# 4_WiFi.net
KiCad netlist of a schematic drawn in Altium Designer
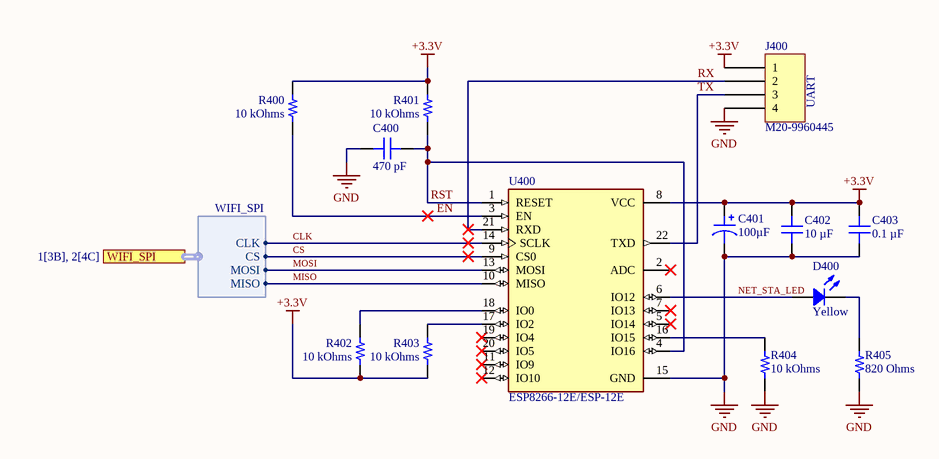
[diagram p0: 4_WiFi.SchDoc]

(export (version "E")
  (design (tool "Eeschema 10.0.6"))
  (components
    (comp (ref "C400")
      (value "470 pF")
      (footprint "CAP 0603_1608")
      (description "CAP CER 470PF 50V X7R 0603")
      (fields
        (field (name "PART NUMBER") "CL10B471KB8NNNC")
        (field (name "CAPACITANCE") "470 pF")
        (field (name "MANUFACTURER") "Samsung Electro-Mechanics")
      )
      (libsource (lib "Celestial Altium Library - altium_library") (part "Capacitor"))
    )
    (comp (ref "C401")
      (value "100µF")
      (footprint "CAP POL 2917_7343")
      (description "CAP TANT 100UF 10% 16V 2917")
      (fields (field (name "PART NUMBER") "TAJD107K016RNJ") (field (name "MANUFACTURER") "AVX Corporation"))
      (libsource (lib "Celestial Altium Library - altium_library") (part "Polarised Capacitor"))
    )
    (comp (ref "C402")
      (value "10 µF")
      (footprint "CAP 0805_2012")
      (description "CAP CER 10UF 10V X7R 0805")
      (fields
        (field (name "PART NUMBER") "CL21B106KPQNNNE")
        (field (name "CAPACITANCE") "10 µF")
        (field (name "MANUFACTURER") "Samsung Electro-Mechanics")
      )
      (libsource (lib "Celestial Altium Library - altium_library") (part "Capacitor"))
    )
    (comp (ref "C403")
      (value "0.1 µF")
      (footprint "CAP 0603_1608")
      (description "CAP CER 0.1UF 25V X7R 0603")
      (fields
        (field (name "PART NUMBER") "CL10B104KA8NNNC")
        (field (name "CAPACITANCE") "0.1 µF")
        (field (name "MANUFACTURER") "Samsung Electro-Mechanics")
      )
      (libsource (lib "Celestial Altium Library - altium_library") (part "Capacitor"))
    )
    (comp (ref "D400")
      (value "Yellow")
      (footprint "LED 0603_1608 YELLOW")
      (description "LED YELLOW DIFFUSED 0603 SMD")
      (fields
        (field (name "PART NUMBER") "LY L29K-H1K2-26-Z")
        (field (name "MANUFACTURER") "OSRAM Opto Semiconductors Inc.")
      )
      (libsource (lib "Celestial Altium Library - altium_library") (part "LED"))
    )
    (comp (ref "J400")
      (value "M20-9960445")
      (footprint "HARWIN M20-9960445")
      (description "CONN HEADER R/A 4POS 2.54MM")
      (fields (field (name "MANUFACTURER") "Harwin Inc."))
      (libsource (lib "Celestial Altium Library - altium_library") (part "4 Pin"))
    )
    (comp (ref "R400")
      (value "10 kOhms")
      (footprint "RES 0603_1608")
      (description "RES SMD 10 KOHM 1% 1/5W 0603")
      (fields
        (field (name "PART NUMBER") "ERJ-P03F1002V")
        (field (name "MANUFACTURER") "Panasonic Electronic Components")
      )
      (libsource (lib "Celestial Altium Library - altium_library") (part "Resistor"))
    )
    (comp (ref "R401")
      (value "10 kOhms")
      (footprint "RES 0603_1608")
      (description "RES SMD 10 KOHM 1% 1/5W 0603")
      (fields
        (field (name "PART NUMBER") "ERJ-P03F1002V")
        (field (name "MANUFACTURER") "Panasonic Electronic Components")
      )
      (libsource (lib "Celestial Altium Library - altium_library") (part "Resistor"))
    )
    (comp (ref "R402")
      (value "10 kOhms")
      (footprint "RES 0603_1608")
      (description "RES SMD 10 KOHM 1% 1/5W 0603")
      (fields
        (field (name "PART NUMBER") "ERJ-P03F1002V")
        (field (name "MANUFACTURER") "Panasonic Electronic Components")
      )
      (libsource (lib "Celestial Altium Library - altium_library") (part "Resistor"))
    )
    (comp (ref "R403")
      (value "10 kOhms")
      (footprint "RES 0603_1608")
      (description "RES SMD 10 KOHM 1% 1/5W 0603")
      (fields
        (field (name "PART NUMBER") "ERJ-P03F1002V")
        (field (name "MANUFACTURER") "Panasonic Electronic Components")
      )
      (libsource (lib "Celestial Altium Library - altium_library") (part "Resistor"))
    )
    (comp (ref "R404")
      (value "10 kOhms")
      (footprint "RES 0603_1608")
      (description "RES SMD 10 KOHM 1% 1/5W 0603")
      (fields
        (field (name "PART NUMBER") "ERJ-P03F1002V")
        (field (name "MANUFACTURER") "Panasonic Electronic Components")
      )
      (libsource (lib "Celestial Altium Library - altium_library") (part "Resistor"))
    )
    (comp (ref "R405")
      (value "820 Ohms")
      (footprint "RES 0603_1608")
      (description "RES SMD 820 OHM 1% 1/10W 0603")
      (fields
        (field (name "PART NUMBER") "ERJ-3EKF8200V")
        (field (name "MANUFACTURER") "Panasonic Electronic Components")
      )
      (libsource (lib "Celestial Altium Library - altium_library") (part "Resistor"))
    )
    (comp (ref "U400")
      (value "ESP8266-12E/ESP-12E")
      (footprint "XCVR_ESP8266-12E/ESP-12E")
      (fields (field (name "MF") "AI-Thinker"))
      (libsource (lib "ESP8266-12E_ESP-12E") (part "ESP8266-12E/ESP-12E"))
    )
  )
  (nets
    (net (code "2") (name "+3.3V") (class "Default")
      (node (ref "C401") (pin "1") (pinfunction "1_1") (pintype "passive"))
      (node (ref "C402") (pin "1") (pinfunction "1_1") (pintype "passive"))
      (node (ref "C403") (pin "2") (pinfunction "2_2") (pintype "passive"))
      (node (ref "J400") (pin "1") (pinfunction "1_1") (pintype "passive"))
      (node (ref "R400") (pin "2") (pinfunction "2_2") (pintype "passive"))
      (node (ref "R401") (pin "2") (pinfunction "2_2") (pintype "passive"))
      (node (ref "R402") (pin "1") (pinfunction "1_1") (pintype "passive"))
      (node (ref "R403") (pin "1") (pinfunction "1_1") (pintype "passive"))
      (node (ref "U400") (pin "8") (pinfunction "VCC_8") (pintype "power_in"))
    )
    (net (code "3") (name "/CLK") (class "Default")
      (node (ref "U400") (pin "14") (pinfunction "SCLK_14") (pintype "input"))
    )
    (net (code "4") (name "/CS") (class "Default")
      (node (ref "U400") (pin "9") (pinfunction "CS0_9") (pintype "input"))
    )
    (net (code "5") (name "/EN") (class "Default")
      (node (ref "R400") (pin "1") (pinfunction "1_1") (pintype "passive"))
      (node (ref "U400") (pin "3") (pinfunction "EN_3") (pintype "input"))
    )
    (net (code "6") (name "/MISO") (class "Default")
      (node (ref "U400") (pin "10") (pinfunction "MISO_10") (pintype "bidirectional"))
    )
    (net (code "7") (name "/MOSI") (class "Default")
      (node (ref "U400") (pin "13") (pinfunction "MOSI_13") (pintype "bidirectional"))
    )
    (net (code "8") (name "/NET_STA_LED") (class "Default")
      (node (ref "D400") (pin "1") (pinfunction "1_1") (pintype "passive"))
      (node (ref "U400") (pin "6") (pinfunction "IO12_6") (pintype "bidirectional"))
    )
    (net (code "9") (name "/RST") (class "Default")
      (node (ref "C400") (pin "2") (pinfunction "2_2") (pintype "passive"))
      (node (ref "R401") (pin "1") (pinfunction "1_1") (pintype "passive"))
      (node (ref "U400") (pin "1") (pinfunction "RESET_1") (pintype "input"))
      (node (ref "U400") (pin "4") (pinfunction "IO16_4") (pintype "bidirectional"))
    )
    (net (code "10") (name "/RX") (class "Default")
      (node (ref "J400") (pin "2") (pinfunction "2_2") (pintype "passive"))
      (node (ref "U400") (pin "21") (pinfunction "RXD_21") (pintype "input"))
    )
    (net (code "11") (name "/TX") (class "Default")
      (node (ref "J400") (pin "3") (pinfunction "3_3") (pintype "passive"))
      (node (ref "U400") (pin "22") (pinfunction "TXD_22") (pintype "output"))
    )
    (net (code "13") (name "GND") (class "Default")
      (node (ref "C400") (pin "1") (pinfunction "1_1") (pintype "passive"))
      (node (ref "C401") (pin "2") (pinfunction "2_2") (pintype "passive"))
      (node (ref "C402") (pin "2") (pinfunction "2_2") (pintype "passive"))
      (node (ref "C403") (pin "1") (pinfunction "1_1") (pintype "passive"))
      (node (ref "J400") (pin "4") (pinfunction "4_4") (pintype "passive"))
      (node (ref "R404") (pin "1") (pinfunction "1_1") (pintype "passive"))
      (node (ref "R405") (pin "1") (pinfunction "1_1") (pintype "passive"))
      (node (ref "U400") (pin "15") (pinfunction "GND_15") (pintype "power_in"))
    )
    (net (code "14") (name "Net-(D400-Pad2)") (class "Default")
      (node (ref "D400") (pin "2") (pinfunction "2_2") (pintype "passive"))
      (node (ref "R405") (pin "2") (pinfunction "2_2") (pintype "passive"))
    )
    (net (code "15") (name "Net-(U400-IO0)") (class "Default")
      (node (ref "R402") (pin "2") (pinfunction "2_2") (pintype "passive"))
      (node (ref "U400") (pin "18") (pinfunction "IO0_18") (pintype "bidirectional"))
    )
    (net (code "16") (name "Net-(U400-IO2)") (class "Default")
      (node (ref "R403") (pin "2") (pinfunction "2_2") (pintype "passive"))
      (node (ref "U400") (pin "17") (pinfunction "IO2_17") (pintype "bidirectional"))
    )
    (net (code "17") (name "Net-(U400-IO15)") (class "Default")
      (node (ref "R404") (pin "2") (pinfunction "2_2") (pintype "passive"))
      (node (ref "U400") (pin "16") (pinfunction "IO15_16") (pintype "bidirectional"))
    )
    (net (code "18") (name "unconnected-(U400-ADC-Pad2)") (class "Default")
      (node (ref "U400") (pin "2") (pinfunction "ADC_2") (pintype "passive+no_connect"))
    )
    (net (code "19") (name "unconnected-(U400-IO4-Pad19)") (class "Default")
      (node (ref "U400") (pin "19") (pinfunction "IO4_19") (pintype "bidirectional+no_connect"))
    )
    (net (code "20") (name "unconnected-(U400-IO5-Pad20)") (class "Default")
      (node (ref "U400") (pin "20") (pinfunction "IO5_20") (pintype "bidirectional+no_connect"))
    )
    (net (code "21") (name "unconnected-(U400-IO9-Pad11)") (class "Default")
      (node (ref "U400") (pin "11") (pinfunction "IO9_11") (pintype "bidirectional+no_connect"))
    )
    (net (code "22") (name "unconnected-(U400-IO10-Pad12)") (class "Default")
      (node (ref "U400") (pin "12") (pinfunction "IO10_12") (pintype "bidirectional+no_connect"))
    )
    (net (code "23") (name "unconnected-(U400-IO13-Pad7)") (class "Default")
      (node (ref "U400") (pin "7") (pinfunction "IO13_7") (pintype "bidirectional+no_connect"))
    )
    (net (code "24") (name "unconnected-(U400-IO14-Pad5)") (class "Default")
      (node (ref "U400") (pin "5") (pinfunction "IO14_5") (pintype "bidirectional+no_connect"))
    )
  )
)
